# FPGA_HDMI_IN_OUT.net
KiCad netlist of a schematic drawn in Altium Designer
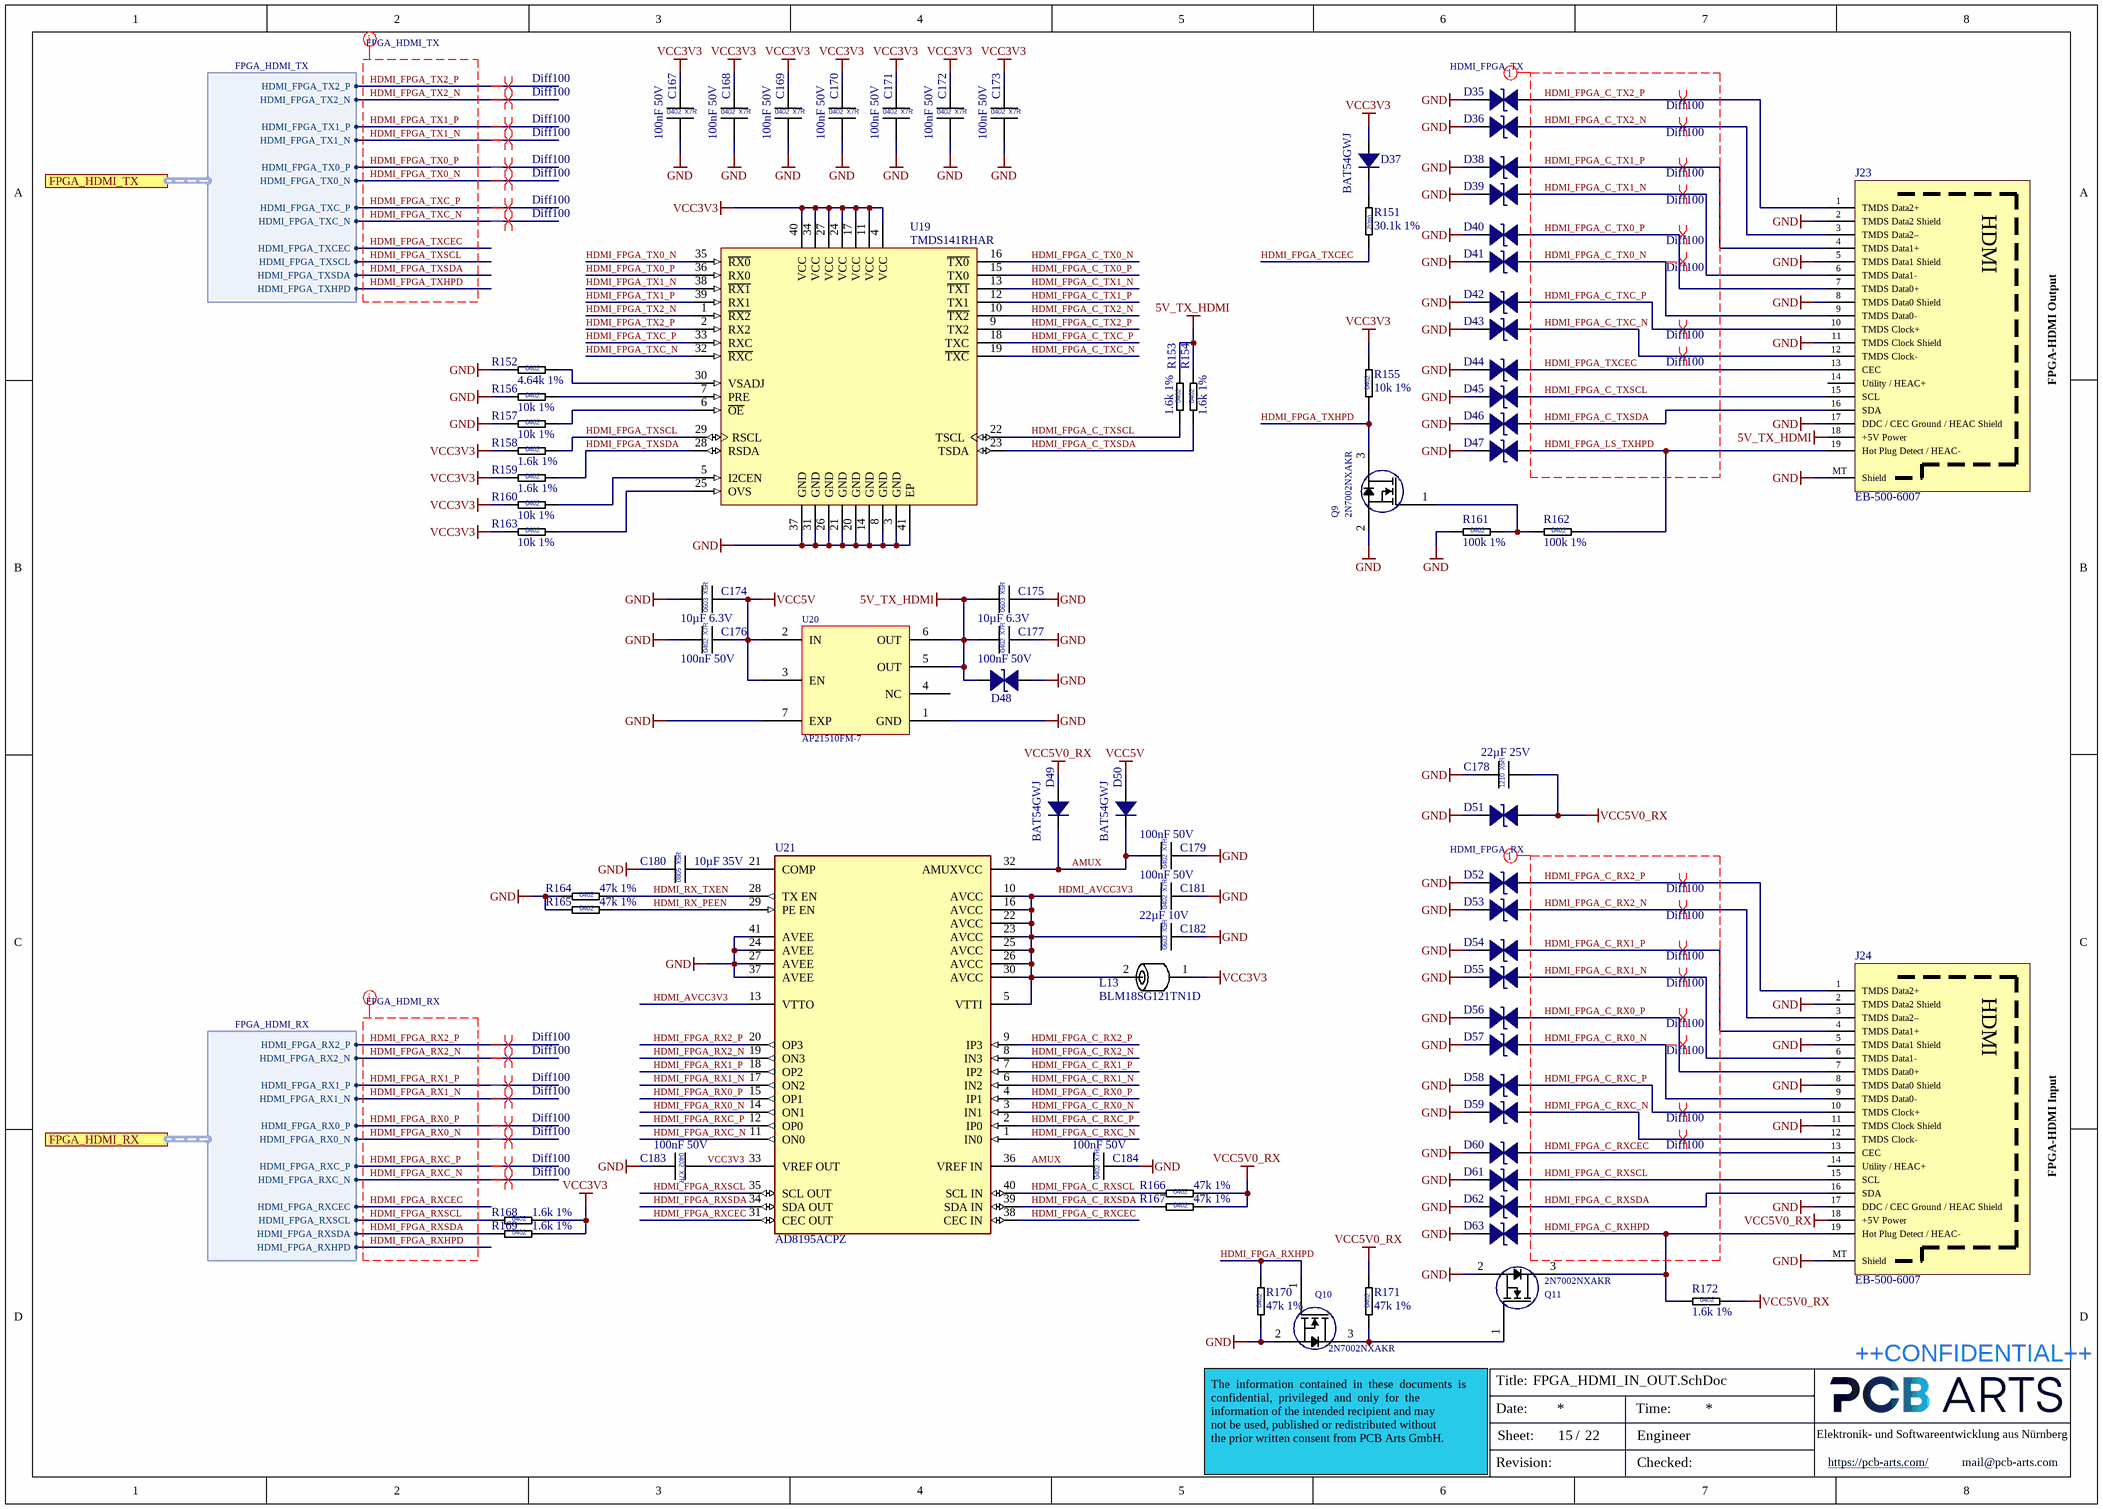
[diagram p0: FPGA_HDMI_IN_OUT.SchDoc]

(export (version "E")
  (design (tool "Eeschema 10.0.6"))
  (components
    (comp (ref "C167")
      (value "100nF 50V")
      (footprint "Cap:CAP_0402_L")
      (description "Multilayer Ceramic Capacitors MLCC - SMD/SMT 0402 50VDC")
      (libsource (lib "") (part "CAP_0402_100nF_50V_1"))
    )
    (comp (ref "C168")
      (value "100nF 50V")
      (footprint "Cap:CAP_0402_L")
      (description "Multilayer Ceramic Capacitors MLCC - SMD/SMT 0402 50VDC")
      (libsource (lib "") (part "CAP_0402_100nF_50V_1"))
    )
    (comp (ref "C169")
      (value "100nF 50V")
      (footprint "Cap:CAP_0402_L")
      (description "Multilayer Ceramic Capacitors MLCC - SMD/SMT 0402 50VDC")
      (libsource (lib "") (part "CAP_0402_100nF_50V_1"))
    )
    (comp (ref "C170")
      (value "100nF 50V")
      (footprint "Cap:CAP_0402_L")
      (description "Multilayer Ceramic Capacitors MLCC - SMD/SMT 0402 50VDC")
      (libsource (lib "") (part "CAP_0402_100nF_50V_1"))
    )
    (comp (ref "C171")
      (value "100nF 50V")
      (footprint "Cap:CAP_0402_L")
      (description "Multilayer Ceramic Capacitors MLCC - SMD/SMT 0402 50VDC")
      (libsource (lib "") (part "CAP_0402_100nF_50V_1"))
    )
    (comp (ref "C172")
      (value "100nF 50V")
      (footprint "Cap:CAP_0402_L")
      (description "Multilayer Ceramic Capacitors MLCC - SMD/SMT 0402 50VDC")
      (libsource (lib "") (part "CAP_0402_100nF_50V_1"))
    )
    (comp (ref "C173")
      (value "100nF 50V")
      (footprint "Cap:CAP_0402_L")
      (description "Multilayer Ceramic Capacitors MLCC - SMD/SMT 0402 50VDC")
      (libsource (lib "") (part "CAP_0402_100nF_50V_1"))
    )
    (comp (ref "C174")
      (value "10µF 6.3V")
      (footprint "Cap:CAP_0603_L")
      (description "Multilayer Ceramic Capacitors MLCC - SMD/SMT 0603 6.3VDC")
      (libsource (lib "Cap") (part "CAP_0603_10µF_6.3V"))
    )
    (comp (ref "C175")
      (value "10µF 6.3V")
      (footprint "Cap:CAP_0603_L")
      (description "Multilayer Ceramic Capacitors MLCC - SMD/SMT 0603 6.3VDC")
      (libsource (lib "Cap") (part "CAP_0603_10µF_6.3V"))
    )
    (comp (ref "C176")
      (value "100nF 50V")
      (footprint "Cap:CAP_0402_L")
      (description "Multilayer Ceramic Capacitors MLCC - SMD/SMT 0402 50VDC")
      (libsource (lib "Cap") (part "CAP_0402_100nF_50V"))
    )
    (comp (ref "C177")
      (value "100nF 50V")
      (footprint "Cap:CAP_0402_L")
      (description "Multilayer Ceramic Capacitors MLCC - SMD/SMT 0402 50VDC")
      (libsource (lib "Cap") (part "CAP_0402_100nF_50V"))
    )
    (comp (ref "C178")
      (value "22µF 25V")
      (footprint "Cap:CAP_1210")
      (description "Multilayer Ceramic Capacitors MLCC - SMD/SMT 1210 25VDC")
      (libsource (lib "Cap") (part "CAP_1210_22µF_25V"))
    )
    (comp (ref "C179")
      (value "100nF 50V")
      (footprint "Cap:CAP_0402_L")
      (description "Multilayer Ceramic Capacitors MLCC - SMD/SMT 0402 50VDC")
      (libsource (lib "Cap") (part "CAP_0402_100nF_50V"))
    )
    (comp (ref "C180")
      (value "10µF 35V")
      (footprint "Cap:CAP_0805")
      (description "Multilayer Ceramic Capacitors MLCC - SMD/SMT 0805 35VDC")
      (libsource (lib "Cap") (part "CAP_0805_10µF_35V"))
    )
    (comp (ref "C181")
      (value "100nF 50V")
      (footprint "Cap:CAP_0402_L")
      (description "Multilayer Ceramic Capacitors MLCC - SMD/SMT 0402 50VDC")
      (libsource (lib "Cap") (part "CAP_0402_100nF_50V"))
    )
    (comp (ref "C182")
      (value "22µF 10V")
      (footprint "Cap:CAP_0603_L")
      (description "Multilayer Ceramic Capacitors MLCC - SMD/SMT 0603 10VDC")
      (libsource (lib "Cap") (part "CAP_0603_22µF_10V"))
    )
    (comp (ref "C183")
      (value "100nF 50V")
      (footprint "Cap:CAP_0402_L")
      (description "Multilayer Ceramic Capacitors MLCC - SMD/SMT 0402 50VDC")
      (libsource (lib "") (part "CAP_0402_100nF_50V_1"))
    )
    (comp (ref "C184")
      (value "100nF 50V")
      (footprint "Cap:CAP_0402_L")
      (description "Multilayer Ceramic Capacitors MLCC - SMD/SMT 0402 50VDC")
      (libsource (lib "Cap") (part "CAP_0402_100nF_50V"))
    )
    (comp (ref "D35")
      (value "CESDP0402UC5VB")
      (footprint "Protec:TVS_0402")
      (description "Low Capacitance ESD Protection Diode 0402")
      (libsource (lib "Protec") (part "CESDP0402UC5VB_TVS Diode 0402"))
    )
    (comp (ref "D36")
      (value "CESDP0402UC5VB")
      (footprint "Protec:TVS_0402")
      (description "Low Capacitance ESD Protection Diode 0402")
      (libsource (lib "Protec") (part "CESDP0402UC5VB_TVS Diode 0402"))
    )
    (comp (ref "D37")
      (value "BAT54GWJ")
      (footprint "Active:SOD123")
      (description "Schottky Diode 30V, 200mA")
      (libsource (lib "Active") (part "BAT54GWJ_Schottky Diode 30V, 200mA"))
    )
    (comp (ref "D38")
      (value "CESDP0402UC5VB")
      (footprint "Protec:TVS_0402")
      (description "Low Capacitance ESD Protection Diode 0402")
      (libsource (lib "Protec") (part "CESDP0402UC5VB_TVS Diode 0402"))
    )
    (comp (ref "D39")
      (value "CESDP0402UC5VB")
      (footprint "Protec:TVS_0402")
      (description "Low Capacitance ESD Protection Diode 0402")
      (libsource (lib "Protec") (part "CESDP0402UC5VB_TVS Diode 0402"))
    )
    (comp (ref "D40")
      (value "CESDP0402UC5VB")
      (footprint "Protec:TVS_0402")
      (description "Low Capacitance ESD Protection Diode 0402")
      (libsource (lib "Protec") (part "CESDP0402UC5VB_TVS Diode 0402"))
    )
    (comp (ref "D41")
      (value "CESDP0402UC5VB")
      (footprint "Protec:TVS_0402")
      (description "Low Capacitance ESD Protection Diode 0402")
      (libsource (lib "Protec") (part "CESDP0402UC5VB_TVS Diode 0402"))
    )
    (comp (ref "D42")
      (value "CESDP0402UC5VB")
      (footprint "Protec:TVS_0402")
      (description "Low Capacitance ESD Protection Diode 0402")
      (libsource (lib "Protec") (part "CESDP0402UC5VB_TVS Diode 0402"))
    )
    (comp (ref "D43")
      (value "CESDP0402UC5VB")
      (footprint "Protec:TVS_0402")
      (description "Low Capacitance ESD Protection Diode 0402")
      (libsource (lib "Protec") (part "CESDP0402UC5VB_TVS Diode 0402"))
    )
    (comp (ref "D44")
      (value "CESDP0402UC5VB")
      (footprint "Protec:TVS_0402")
      (description "Low Capacitance ESD Protection Diode 0402")
      (libsource (lib "Protec") (part "CESDP0402UC5VB_TVS Diode 0402"))
    )
    (comp (ref "D45")
      (value "CESDP0402UC5VB")
      (footprint "Protec:TVS_0402")
      (description "Low Capacitance ESD Protection Diode 0402")
      (libsource (lib "Protec") (part "CESDP0402UC5VB_TVS Diode 0402"))
    )
    (comp (ref "D46")
      (value "CESDP0402UC5VB")
      (footprint "Protec:TVS_0402")
      (description "Low Capacitance ESD Protection Diode 0402")
      (libsource (lib "Protec") (part "CESDP0402UC5VB_TVS Diode 0402"))
    )
    (comp (ref "D47")
      (value "CESDP0402UC5VB")
      (footprint "Protec:TVS_0402")
      (description "Low Capacitance ESD Protection Diode 0402")
      (libsource (lib "Protec") (part "CESDP0402UC5VB_TVS Diode 0402"))
    )
    (comp (ref "D48")
      (value "CESDP0402UC5VB")
      (footprint "Protec:TVS_0402")
      (description "Low Capacitance ESD Protection Diode 0402")
      (libsource (lib "Protec") (part "CESDP0402UC5VB_TVS Diode 0402"))
    )
    (comp (ref "D49")
      (value "BAT54GWJ")
      (footprint "Active:SOD123")
      (description "Schottky Diode 30V, 200mA")
      (libsource (lib "Active") (part "BAT54GWJ_Schottky Diode 30V, 200mA"))
    )
    (comp (ref "D50")
      (value "BAT54GWJ")
      (footprint "Active:SOD123")
      (description "Schottky Diode 30V, 200mA")
      (libsource (lib "Active") (part "BAT54GWJ_Schottky Diode 30V, 200mA"))
    )
    (comp (ref "D51")
      (value "CESDP0402UC5VB")
      (footprint "Protec:TVS_0402")
      (description "Low Capacitance ESD Protection Diode 0402")
      (libsource (lib "Protec") (part "CESDP0402UC5VB_TVS Diode 0402"))
    )
    (comp (ref "D52")
      (value "CESDP0402UC5VB")
      (footprint "Protec:TVS_0402")
      (description "Low Capacitance ESD Protection Diode 0402")
      (libsource (lib "Protec") (part "CESDP0402UC5VB_TVS Diode 0402"))
    )
    (comp (ref "D53")
      (value "CESDP0402UC5VB")
      (footprint "Protec:TVS_0402")
      (description "Low Capacitance ESD Protection Diode 0402")
      (libsource (lib "Protec") (part "CESDP0402UC5VB_TVS Diode 0402"))
    )
    (comp (ref "D54")
      (value "CESDP0402UC5VB")
      (footprint "Protec:TVS_0402")
      (description "Low Capacitance ESD Protection Diode 0402")
      (libsource (lib "Protec") (part "CESDP0402UC5VB_TVS Diode 0402"))
    )
    (comp (ref "D55")
      (value "CESDP0402UC5VB")
      (footprint "Protec:TVS_0402")
      (description "Low Capacitance ESD Protection Diode 0402")
      (libsource (lib "Protec") (part "CESDP0402UC5VB_TVS Diode 0402"))
    )
    (comp (ref "D56")
      (value "CESDP0402UC5VB")
      (footprint "Protec:TVS_0402")
      (description "Low Capacitance ESD Protection Diode 0402")
      (libsource (lib "Protec") (part "CESDP0402UC5VB_TVS Diode 0402"))
    )
    (comp (ref "D57")
      (value "CESDP0402UC5VB")
      (footprint "Protec:TVS_0402")
      (description "Low Capacitance ESD Protection Diode 0402")
      (libsource (lib "Protec") (part "CESDP0402UC5VB_TVS Diode 0402"))
    )
    (comp (ref "D58")
      (value "CESDP0402UC5VB")
      (footprint "Protec:TVS_0402")
      (description "Low Capacitance ESD Protection Diode 0402")
      (libsource (lib "Protec") (part "CESDP0402UC5VB_TVS Diode 0402"))
    )
    (comp (ref "D59")
      (value "CESDP0402UC5VB")
      (footprint "Protec:TVS_0402")
      (description "Low Capacitance ESD Protection Diode 0402")
      (libsource (lib "Protec") (part "CESDP0402UC5VB_TVS Diode 0402"))
    )
    (comp (ref "D60")
      (value "CESDP0402UC5VB")
      (footprint "Protec:TVS_0402")
      (description "Low Capacitance ESD Protection Diode 0402")
      (libsource (lib "Protec") (part "CESDP0402UC5VB_TVS Diode 0402"))
    )
    (comp (ref "D61")
      (value "CESDP0402UC5VB")
      (footprint "Protec:TVS_0402")
      (description "Low Capacitance ESD Protection Diode 0402")
      (libsource (lib "Protec") (part "CESDP0402UC5VB_TVS Diode 0402"))
    )
    (comp (ref "D62")
      (value "CESDP0402UC5VB")
      (footprint "Protec:TVS_0402")
      (description "Low Capacitance ESD Protection Diode 0402")
      (libsource (lib "Protec") (part "CESDP0402UC5VB_TVS Diode 0402"))
    )
    (comp (ref "D63")
      (value "CESDP0402UC5VB")
      (footprint "Protec:TVS_0402")
      (description "Low Capacitance ESD Protection Diode 0402")
      (libsource (lib "Protec") (part "CESDP0402UC5VB_TVS Diode 0402"))
    )
    (comp (ref "J23")
      (value "EB-500-6007")
      (footprint "Conn:Elecbee EB-500-6007")
      (description "HDMI Connector Female Vertical 19 Pin")
      (libsource (lib "Conn") (part "EB-500-6007_HDMI Connector 19Pin Vertical THT"))
    )
    (comp (ref "J24")
      (value "EB-500-6007")
      (footprint "Conn:Elecbee EB-500-6007")
      (description "HDMI Connector Female Vertical 19 Pin")
      (libsource (lib "Conn") (part "EB-500-6007_HDMI Connector 19Pin Vertical THT"))
    )
    (comp (ref "L13")
      (value "BLM18SG121TN1D")
      (footprint "Indc:L_0603")
      (description "Ferritperlen BLM18_xN 0603 100MHz 120Ohm 3000mA 25mOhm RSER")
      (libsource (lib "Indc") (part "BLM18SG121TN1D_Ferrite Beads 0603 120Ohms 3000mA"))
    )
    (comp (ref "Q9")
      (value "2N7002NXAKR")
      (footprint "trans:SOT95P251X112-3N")
      (description "MOSFET 60V SGL N-CH TRENCHMOS")
      (libsource (lib "Trans") (part "2N7002NXAKR_MOSFET 60V SGL N-CH TRENCHMOS"))
    )
    (comp (ref "Q10")
      (value "2N7002NXAKR")
      (footprint "trans:SOT95P251X112-3N")
      (description "MOSFET 60V SGL N-CH TRENCHMOS")
      (libsource (lib "Trans") (part "2N7002NXAKR_MOSFET 60V SGL N-CH TRENCHMOS"))
    )
    (comp (ref "Q11")
      (value "2N7002NXAKR")
      (footprint "trans:SOT95P251X112-3N")
      (description "MOSFET 60V SGL N-CH TRENCHMOS")
      (libsource (lib "") (part "2N7002NXAKR_MOSFET 60V SGL N-CH TRENCHMOS_1"))
    )
    (comp (ref "R151")
      (value "30.1k 1%")
      (footprint "Res:RES_0402_L")
      (description "Thick Film Resistors - SMD 30.1kOhm 1%")
      (libsource (lib "Res") (part "RES_0402_30.1k_1%"))
    )
    (comp (ref "R152")
      (value "4.64k 1%")
      (footprint "Res:RES_0402_L")
      (description "Thick Film Resistors - SMD 4.64kOhm 1%")
      (libsource (lib "Res") (part "RES_0402_4.64k_1%"))
    )
    (comp (ref "R153")
      (value "1.6k 1%")
      (footprint "Res:RES_0402_L")
      (description "Thick Film Resistors - SMD 1.6kOhm 1%")
      (libsource (lib "Res") (part "RES_0402_1.6k_1%"))
    )
    (comp (ref "R154")
      (value "1.6k 1%")
      (footprint "Res:RES_0402_L")
      (description "Thick Film Resistors - SMD 1.6kOhm 1%")
      (libsource (lib "Res") (part "RES_0402_1.6k_1%"))
    )
    (comp (ref "R155")
      (value "10k 1%")
      (footprint "Res:RES_0402_L")
      (description "Thick Film Resistors - SMD 10kOhm 1%")
      (libsource (lib "Res") (part "RES_0402_10k_1%"))
    )
    (comp (ref "R156")
      (value "10k 1%")
      (footprint "Res:RES_0402_L")
      (description "Thick Film Resistors - SMD 10kOhm 1%")
      (libsource (lib "Res") (part "RES_0402_10k_1%"))
    )
    (comp (ref "R157")
      (value "10k 1%")
      (footprint "Res:RES_0402_L")
      (description "Thick Film Resistors - SMD 10kOhm 1%")
      (libsource (lib "Res") (part "RES_0402_10k_1%"))
    )
    (comp (ref "R158")
      (value "1.6k 1%")
      (footprint "Res:RES_0402_L")
      (description "Thick Film Resistors - SMD 1.6kOhm 1%")
      (libsource (lib "Res") (part "RES_0402_1.6k_1%"))
    )
    (comp (ref "R159")
      (value "1.6k 1%")
      (footprint "Res:RES_0402_L")
      (description "Thick Film Resistors - SMD 1.6kOhm 1%")
      (libsource (lib "Res") (part "RES_0402_1.6k_1%"))
    )
    (comp (ref "R160")
      (value "10k 1%")
      (footprint "Res:RES_0402_L")
      (description "Thick Film Resistors - SMD 10kOhm 1%")
      (libsource (lib "Res") (part "RES_0402_10k_1%"))
    )
    (comp (ref "R161")
      (value "100k 1%")
      (footprint "Res:RES_0402_L")
      (description "Thick Film Resistors - SMD 100kOhm 1%")
      (libsource (lib "Res") (part "RES_0402_100k_1%"))
    )
    (comp (ref "R162")
      (value "100k 1%")
      (footprint "Res:RES_0402_L")
      (description "Thick Film Resistors - SMD 100kOhm 1%")
      (libsource (lib "Res") (part "RES_0402_100k_1%"))
    )
    (comp (ref "R163")
      (value "10k 1%")
      (footprint "Res:RES_0402_L")
      (description "Thick Film Resistors - SMD 10kOhm 1%")
      (libsource (lib "Res") (part "RES_0402_10k_1%"))
    )
    (comp (ref "R164")
      (value "47k 1%")
      (footprint "Res:RES_0402_L")
      (description "Thick Film Resistors - SMD 47kOhm 1%")
      (libsource (lib "Res") (part "RES_0402_47k_1%"))
    )
    (comp (ref "R165")
      (value "47k 1%")
      (footprint "Res:RES_0402_L")
      (description "Thick Film Resistors - SMD 47kOhm 1%")
      (libsource (lib "Res") (part "RES_0402_47k_1%"))
    )
    (comp (ref "R166")
      (value "47k 1%")
      (footprint "Res:RES_0402_L")
      (description "Thick Film Resistors - SMD 47kOhm 1%")
      (libsource (lib "Res") (part "RES_0402_47k_1%"))
    )
    (comp (ref "R167")
      (value "47k 1%")
      (footprint "Res:RES_0402_L")
      (description "Thick Film Resistors - SMD 47kOhm 1%")
      (libsource (lib "Res") (part "RES_0402_47k_1%"))
    )
    (comp (ref "R168")
      (value "1.6k 1%")
      (footprint "Res:RES_0402_L")
      (description "Thick Film Resistors - SMD 1.6kOhm 1%")
      (libsource (lib "Res") (part "RES_0402_1.6k_1%"))
    )
    (comp (ref "R169")
      (value "1.6k 1%")
      (footprint "Res:RES_0402_L")
      (description "Thick Film Resistors - SMD 1.6kOhm 1%")
      (libsource (lib "Res") (part "RES_0402_1.6k_1%"))
    )
    (comp (ref "R170")
      (value "47k 1%")
      (footprint "Res:RES_0402_L")
      (description "Thick Film Resistors - SMD 47kOhm 1%")
      (libsource (lib "Res") (part "RES_0402_47k_1%"))
    )
    (comp (ref "R171")
      (value "47k 1%")
      (footprint "Res:RES_0402_L")
      (description "Thick Film Resistors - SMD 47kOhm 1%")
      (libsource (lib "Res") (part "RES_0402_47k_1%"))
    )
    (comp (ref "R172")
      (value "1.6k 1%")
      (footprint "Res:RES_0402_L")
      (description "Thick Film Resistors - SMD 1.6kOhm 1%")
      (libsource (lib "Res") (part "RES_0402_1.6k_1%"))
    )
    (comp (ref "U19")
      (value "TMDS141RHAR")
      (footprint "Digital:QFN50P600X600X100-41N")
      (description "HDMI Hider, 130 mA, 6 kV, 0 to +70 degC, 40-pin QFN")
      (libsource (lib "Digital") (part "TMDS141RHAR_HDMI Hider, 130 mA, 6 kV, 0 to +70 degC, 40-pin QFN"))
    )
    (comp (ref "U20")
      (value "AP21510FM-7")
      (footprint "Power:QFN50P201X181X60_HS-7N")
      (description "Power Switch ICs - Power Distribution 0.5A SGL Ch USB 2.0 Curr Limited Switch")
      (libsource (lib "Power") (part "AP21510FM-7_Power Switch ICs - Power Distribution Load Switch"))
    )
    (comp (ref "U21")
      (value "AD8195ACPZ")
      (footprint "Digital:QFN50P600X600X100-41N")
      (description "IC VIDEO HDMI/DVI BUFFER 40LFCSP")
      (libsource (lib "Digital") (part "AD8195ACPZ_IC VIDEO HDMI/DVI BUFFER 40LFCSP"))
    )
  )
  (nets
    (net (code "3") (name "/AMUX") (class "Default")
      (node (ref "C179") (pin "1") (pinfunction "1_1") (pintype "passive"))
      (node (ref "C184") (pin "1") (pinfunction "1_1") (pintype "passive"))
      (node (ref "D49") (pin "1") (pinfunction "1_1") (pintype "passive"))
      (node (ref "D50") (pin "1") (pinfunction "1_1") (pintype "passive"))
      (node (ref "U21") (pin "32") (pinfunction "AMUXVCC_32") (pintype "power_in"))
      (node (ref "U21") (pin "36") (pinfunction "VREF_IN_36") (pintype "passive"))
    )
    (net (code "4") (name "/HDMI_AVCC3V3") (class "Default")
      (node (ref "C181") (pin "1") (pinfunction "1_1") (pintype "passive"))
      (node (ref "C182") (pin "1") (pinfunction "1_1") (pintype "passive"))
      (node (ref "L13") (pin "2") (pinfunction "2_2") (pintype "passive"))
      (node (ref "U21") (pin "10") (pinfunction "AVCC_10") (pintype "power_in"))
      (node (ref "U21") (pin "13") (pinfunction "VTTO_13") (pintype "power_in"))
      (node (ref "U21") (pin "16") (pinfunction "AVCC_16") (pintype "power_in"))
      (node (ref "U21") (pin "22") (pinfunction "AVCC_22") (pintype "power_in"))
      (node (ref "U21") (pin "23") (pinfunction "AVCC_23") (pintype "power_in"))
      (node (ref "U21") (pin "25") (pinfunction "AVCC_25") (pintype "power_in"))
      (node (ref "U21") (pin "26") (pinfunction "AVCC_26") (pintype "power_in"))
      (node (ref "U21") (pin "30") (pinfunction "AVCC_30") (pintype "power_in"))
      (node (ref "U21") (pin "5") (pinfunction "VTTI_5") (pintype "power_in"))
    )
    (net (code "5") (name "/HDMI_FPGA_C_RX0_N") (class "Default")
      (node (ref "D57") (pin "2") (pinfunction "2_2") (pintype "passive"))
      (node (ref "J24") (pin "9") (pinfunction "TMDS_Data0-_9") (pintype "passive"))
      (node (ref "U21") (pin "3") (pinfunction "IN1_3") (pintype "input"))
    )
    (net (code "6") (name "/HDMI_FPGA_C_RX0_P") (class "Default")
      (node (ref "D56") (pin "2") (pinfunction "2_2") (pintype "passive"))
      (node (ref "J24") (pin "7") (pinfunction "TMDS_Data0+_7") (pintype "passive"))
      (node (ref "U21") (pin "4") (pinfunction "IP1_4") (pintype "input"))
    )
    (net (code "7") (name "/HDMI_FPGA_C_RX1_N") (class "Default")
      (node (ref "D55") (pin "2") (pinfunction "2_2") (pintype "passive"))
      (node (ref "J24") (pin "6") (pinfunction "TMDS_Data1-_6") (pintype "passive"))
      (node (ref "U21") (pin "6") (pinfunction "IN2_6") (pintype "input"))
    )
    (net (code "8") (name "/HDMI_FPGA_C_RX1_P") (class "Default")
      (node (ref "D54") (pin "2") (pinfunction "2_2") (pintype "passive"))
      (node (ref "J24") (pin "4") (pinfunction "TMDS_Data1+_4") (pintype "passive"))
      (node (ref "U21") (pin "7") (pinfunction "IP2_7") (pintype "input"))
    )
    (net (code "9") (name "/HDMI_FPGA_C_RX2_N") (class "Default")
      (node (ref "D53") (pin "2") (pinfunction "2_2") (pintype "passive"))
      (node (ref "J24") (pin "3") (pinfunction "TMDS_Data2–_3") (pintype "passive"))
      (node (ref "U21") (pin "8") (pinfunction "IN3_8") (pintype "input"))
    )
    (net (code "10") (name "/HDMI_FPGA_C_RX2_P") (class "Default")
      (node (ref "D52") (pin "2") (pinfunction "2_2") (pintype "passive"))
      (node (ref "J24") (pin "1") (pinfunction "TMDS_Data2+_1") (pintype "passive"))
      (node (ref "U21") (pin "9") (pinfunction "IP3_9") (pintype "input"))
    )
    (net (code "11") (name "/HDMI_FPGA_C_RXCEC") (class "Default")
      (node (ref "D60") (pin "2") (pinfunction "2_2") (pintype "passive"))
      (node (ref "J24") (pin "13") (pinfunction "CEC_13") (pintype "passive"))
      (node (ref "U21") (pin "38") (pinfunction "CEC_IN_38") (pintype "bidirectional"))
    )
    (net (code "12") (name "/HDMI_FPGA_C_RXC_N") (class "Default")
      (node (ref "D59") (pin "2") (pinfunction "2_2") (pintype "passive"))
      (node (ref "J24") (pin "12") (pinfunction "TMDS_Clock-_12") (pintype "passive"))
      (node (ref "U21") (pin "1") (pinfunction "IN0_1") (pintype "input"))
    )
    (net (code "13") (name "/HDMI_FPGA_C_RXC_P") (class "Default")
      (node (ref "D58") (pin "2") (pinfunction "2_2") (pintype "passive"))
      (node (ref "J24") (pin "10") (pinfunction "TMDS_Clock+_10") (pintype "passive"))
      (node (ref "U21") (pin "2") (pinfunction "IP0_2") (pintype "input"))
    )
    (net (code "14") (name "/HDMI_FPGA_C_RXHPD") (class "Default")
      (node (ref "D63") (pin "2") (pinfunction "2_2") (pintype "passive"))
      (node (ref "J24") (pin "19") (pinfunction "Hot_Plug_Detect_/_HEAC-_19") (pintype "passive"))
      (node (ref "Q11") (pin "3") (pinfunction "D_3") (pintype "passive"))
      (node (ref "R172") (pin "1") (pinfunction "1_1") (pintype "passive"))
    )
    (net (code "15") (name "/HDMI_FPGA_C_RXSCL") (class "Default")
      (node (ref "D61") (pin "2") (pinfunction "2_2") (pintype "passive"))
      (node (ref "J24") (pin "15") (pinfunction "SCL_15") (pintype "passive"))
      (node (ref "R166") (pin "1") (pinfunction "1_1") (pintype "passive"))
      (node (ref "U21") (pin "40") (pinfunction "SCL_IN_40") (pintype "bidirectional"))
    )
    (net (code "16") (name "/HDMI_FPGA_C_RXSDA") (class "Default")
      (node (ref "D62") (pin "2") (pinfunction "2_2") (pintype "passive"))
      (node (ref "J24") (pin "16") (pinfunction "SDA_16") (pintype "passive"))
      (node (ref "R167") (pin "1") (pinfunction "1_1") (pintype "passive"))
      (node (ref "U21") (pin "39") (pinfunction "SDA_IN_39") (pintype "bidirectional"))
    )
    (net (code "17") (name "/HDMI_FPGA_C_TX0_N") (class "Default")
      (node (ref "D41") (pin "2") (pinfunction "2_2") (pintype "passive"))
      (node (ref "J23") (pin "9") (pinfunction "TMDS_Data0-_9") (pintype "passive"))
      (node (ref "U19") (pin "16") (pinfunction "~{TX0}_16") (pintype "tri_state"))
    )
    (net (code "18") (name "/HDMI_FPGA_C_TX0_P") (class "Default")
      (node (ref "D40") (pin "2") (pinfunction "2_2") (pintype "passive"))
      (node (ref "J23") (pin "7") (pinfunction "TMDS_Data0+_7") (pintype "passive"))
      (node (ref "U19") (pin "15") (pinfunction "TX0_15") (pintype "tri_state"))
    )
    (net (code "19") (name "/HDMI_FPGA_C_TX1_N") (class "Default")
      (node (ref "D39") (pin "2") (pinfunction "2_2") (pintype "passive"))
      (node (ref "J23") (pin "6") (pinfunction "TMDS_Data1-_6") (pintype "passive"))
      (node (ref "U19") (pin "13") (pinfunction "~{TX1}_13") (pintype "tri_state"))
    )
    (net (code "20") (name "/HDMI_FPGA_C_TX1_P") (class "Default")
      (node (ref "D38") (pin "2") (pinfunction "2_2") (pintype "passive"))
      (node (ref "J23") (pin "4") (pinfunction "TMDS_Data1+_4") (pintype "passive"))
      (node (ref "U19") (pin "12") (pinfunction "TX1_12") (pintype "tri_state"))
    )
    (net (code "21") (name "/HDMI_FPGA_C_TX2_N") (class "Default")
      (node (ref "D36") (pin "2") (pinfunction "2_2") (pintype "passive"))
      (node (ref "J23") (pin "3") (pinfunction "TMDS_Data2–_3") (pintype "passive"))
      (node (ref "U19") (pin "10") (pinfunction "~{TX2}_10") (pintype "tri_state"))
    )
    (net (code "22") (name "/HDMI_FPGA_C_TX2_P") (class "Default")
      (node (ref "D35") (pin "2") (pinfunction "2_2") (pintype "passive"))
      (node (ref "J23") (pin "1") (pinfunction "TMDS_Data2+_1") (pintype "passive"))
      (node (ref "U19") (pin "9") (pinfunction "TX2_9") (pintype "tri_state"))
    )
    (net (code "23") (name "/HDMI_FPGA_C_TXC_N") (class "Default")
      (node (ref "D43") (pin "2") (pinfunction "2_2") (pintype "passive"))
      (node (ref "J23") (pin "12") (pinfunction "TMDS_Clock-_12") (pintype "passive"))
      (node (ref "U19") (pin "19") (pinfunction "~{TXC}_19") (pintype "tri_state"))
    )
    (net (code "24") (name "/HDMI_FPGA_C_TXC_P") (class "Default")
      (node (ref "D42") (pin "2") (pinfunction "2_2") (pintype "passive"))
      (node (ref "J23") (pin "10") (pinfunction "TMDS_Clock+_10") (pintype "passive"))
      (node (ref "U19") (pin "18") (pinfunction "TXC_18") (pintype "tri_state"))
    )
    (net (code "25") (name "/HDMI_FPGA_C_TXSCL") (class "Default")
      (node (ref "D45") (pin "2") (pinfunction "2_2") (pintype "passive"))
      (node (ref "J23") (pin "15") (pinfunction "SCL_15") (pintype "passive"))
      (node (ref "R153") (pin "1") (pinfunction "1_1") (pintype "passive"))
      (node (ref "U19") (pin "22") (pinfunction "TSCL_22") (pintype "bidirectional"))
    )
    (net (code "26") (name "/HDMI_FPGA_C_TXSDA") (class "Default")
      (node (ref "D46") (pin "2") (pinfunction "2_2") (pintype "passive"))
      (node (ref "J23") (pin "16") (pinfunction "SDA_16") (pintype "passive"))
      (node (ref "R154") (pin "1") (pinfunction "1_1") (pintype "passive"))
      (node (ref "U19") (pin "23") (pinfunction "TSDA_23") (pintype "bidirectional"))
    )
    (net (code "27") (name "/HDMI_FPGA_LS_TXHPD") (class "Default")
      (node (ref "D47") (pin "2") (pinfunction "2_2") (pintype "passive"))
      (node (ref "J23") (pin "19") (pinfunction "Hot_Plug_Detect_/_HEAC-_19") (pintype "passive"))
      (node (ref "R162") (pin "2") (pinfunction "2_2") (pintype "passive"))
    )
    (net (code "28") (name "/HDMI_FPGA_RX0_N") (class "Default")
      (node (ref "U21") (pin "14") (pinfunction "ON1_14") (pintype "output"))
    )
    (net (code "29") (name "/HDMI_FPGA_RX0_P") (class "Default")
      (node (ref "U21") (pin "15") (pinfunction "OP1_15") (pintype "output"))
    )
    (net (code "30") (name "/HDMI_FPGA_RX1_N") (class "Default")
      (node (ref "U21") (pin "17") (pinfunction "ON2_17") (pintype "output"))
    )
    (net (code "31") (name "/HDMI_FPGA_RX1_P") (class "Default")
      (node (ref "U21") (pin "18") (pinfunction "OP2_18") (pintype "output"))
    )
    (net (code "32") (name "/HDMI_FPGA_RX2_N") (class "Default")
      (node (ref "U21") (pin "19") (pinfunction "ON3_19") (pintype "output"))
    )
    (net (code "33") (name "/HDMI_FPGA_RX2_P") (class "Default")
      (node (ref "U21") (pin "20") (pinfunction "OP3_20") (pintype "output"))
    )
    (net (code "34") (name "/HDMI_FPGA_RXCEC") (class "Default")
      (node (ref "U21") (pin "31") (pinfunction "CEC_OUT_31") (pintype "bidirectional"))
    )
    (net (code "35") (name "/HDMI_FPGA_RXC_N") (class "Default")
      (node (ref "U21") (pin "11") (pinfunction "ON0_11") (pintype "output"))
    )
    (net (code "36") (name "/HDMI_FPGA_RXC_P") (class "Default")
      (node (ref "U21") (pin "12") (pinfunction "OP0_12") (pintype "output"))
    )
    (net (code "37") (name "/HDMI_FPGA_RXHPD") (class "Default")
      (node (ref "Q10") (pin "1") (pinfunction "G_1") (pintype "passive"))
      (node (ref "R170") (pin "2") (pinfunction "2_2") (pintype "passive"))
    )
    (net (code "38") (name "/HDMI_FPGA_RXSCL") (class "Default")
      (node (ref "R168") (pin "1") (pinfunction "1_1") (pintype "passive"))
      (node (ref "U21") (pin "35") (pinfunction "SCL_OUT_35") (pintype "bidirectional"))
    )
    (net (code "39") (name "/HDMI_FPGA_RXSDA") (class "Default")
      (node (ref "R169") (pin "1") (pinfunction "1_1") (pintype "passive"))
      (node (ref "U21") (pin "34") (pinfunction "SDA_OUT_34") (pintype "bidirectional"))
    )
    (net (code "40") (name "/HDMI_FPGA_TX0_N") (class "Default")
      (node (ref "U19") (pin "35") (pinfunction "~{RX0}_35") (pintype "input"))
    )
    (net (code "41") (name "/HDMI_FPGA_TX0_P") (class "Default")
      (node (ref "U19") (pin "36") (pinfunction "RX0_36") (pintype "input"))
    )
    (net (code "42") (name "/HDMI_FPGA_TX1_N") (class "Default")
      (node (ref "U19") (pin "38") (pinfunction "~{RX1}_38") (pintype "input"))
    )
    (net (code "43") (name "/HDMI_FPGA_TX1_P") (class "Default")
      (node (ref "U19") (pin "39") (pinfunction "RX1_39") (pintype "input"))
    )
    (net (code "44") (name "/HDMI_FPGA_TX2_N") (class "Default")
      (node (ref "U19") (pin "1") (pinfunction "~{RX2}_1") (pintype "input"))
    )
    (net (code "45") (name "/HDMI_FPGA_TX2_P") (class "Default")
      (node (ref "U19") (pin "2") (pinfunction "RX2_2") (pintype "input"))
    )
    (net (code "46") (name "/HDMI_FPGA_TXCEC") (class "Default")
      (node (ref "D44") (pin "2") (pinfunction "2_2") (pintype "passive"))
      (node (ref "J23") (pin "13") (pinfunction "CEC_13") (pintype "passive"))
      (node (ref "R151") (pin "2") (pinfunction "2_2") (pintype "passive"))
    )
    (net (code "47") (name "/HDMI_FPGA_TXC_N") (class "Default")
      (node (ref "U19") (pin "32") (pinfunction "~{RXC}_32") (pintype "input"))
    )
    (net (code "48") (name "/HDMI_FPGA_TXC_P") (class "Default")
      (node (ref "U19") (pin "33") (pinfunction "RXC_33") (pintype "input"))
    )
    (net (code "49") (name "/HDMI_FPGA_TXHPD") (class "Default")
      (node (ref "Q9") (pin "3") (pinfunction "D_3") (pintype "passive"))
      (node (ref "R155") (pin "1") (pinfunction "1_1") (pintype "passive"))
    )
    (net (code "50") (name "/HDMI_FPGA_TXSCL") (class "Default")
      (node (ref "R158") (pin "2") (pinfunction "2_2") (pintype "passive"))
      (node (ref "U19") (pin "29") (pinfunction "RSCL_29") (pintype "bidirectional"))
    )
    (net (code "51") (name "/HDMI_FPGA_TXSDA") (class "Default")
      (node (ref "R159") (pin "2") (pinfunction "2_2") (pintype "passive"))
      (node (ref "U19") (pin "28") (pinfunction "RSDA_28") (pintype "bidirectional"))
    )
    (net (code "52") (name "/HDMI_RX_PEEN") (class "Default")
      (node (ref "R165") (pin "2") (pinfunction "2_2") (pintype "passive"))
      (node (ref "U21") (pin "29") (pinfunction "PE_EN_29") (pintype "input"))
    )
    (net (code "53") (name "/HDMI_RX_TXEN") (class "Default")
      (node (ref "R164") (pin "2") (pinfunction "2_2") (pintype "passive"))
      (node (ref "U21") (pin "28") (pinfunction "TX_EN_28") (pintype "output"))
    )
    (net (code "56") (name "5V_TX_HDMI") (class "Default")
      (node (ref "C175") (pin "1") (pinfunction "1_1") (pintype "passive"))
      (node (ref "C177") (pin "1") (pinfunction "1_1") (pintype "passive"))
      (node (ref "D48") (pin "1") (pinfunction "1_1") (pintype "passive"))
      (node (ref "J23") (pin "18") (pinfunction "+5V_Power_18") (pintype "passive"))
      (node (ref "R153") (pin "2") (pinfunction "2_2") (pintype "passive"))
      (node (ref "R154") (pin "2") (pinfunction "2_2") (pintype "passive"))
      (node (ref "U20") (pin "5") (pinfunction "OUT_5") (pintype "power_in"))
      (node (ref "U20") (pin "6") (pinfunction "OUT_6") (pintype "power_in"))
    )
    (net (code "57") (name "GND") (class "Default")
      (node (ref "C167") (pin "2") (pinfunction "2_2") (pintype "passive"))
      (node (ref "C168") (pin "2") (pinfunction "2_2") (pintype "passive"))
      (node (ref "C169") (pin "2") (pinfunction "2_2") (pintype "passive"))
      (node (ref "C170") (pin "2") (pinfunction "2_2") (pintype "passive"))
      (node (ref "C171") (pin "2") (pinfunction "2_2") (pintype "passive"))
      (node (ref "C172") (pin "2") (pinfunction "2_2") (pintype "passive"))
      (node (ref "C173") (pin "2") (pinfunction "2_2") (pintype "passive"))
      (node (ref "C174") (pin "1") (pinfunction "1_1") (pintype "passive"))
      (node (ref "C175") (pin "2") (pinfunction "2_2") (pintype "passive"))
      (node (ref "C176") (pin "1") (pinfunction "1_1") (pintype "passive"))
      (node (ref "C177") (pin "2") (pinfunction "2_2") (pintype "passive"))
      (node (ref "C178") (pin "1") (pinfunction "1_1") (pintype "passive"))
      (node (ref "C179") (pin "2") (pinfunction "2_2") (pintype "passive"))
      (node (ref "C180") (pin "1") (pinfunction "1_1") (pintype "passive"))
      (node (ref "C181") (pin "2") (pinfunction "2_2") (pintype "passive"))
      (node (ref "C182") (pin "2") (pinfunction "2_2") (pintype "passive"))
      (node (ref "C183") (pin "2") (pinfunction "2_2") (pintype "passive"))
      (node (ref "C184") (pin "2") (pinfunction "2_2") (pintype "passive"))
      (node (ref "D35") (pin "1") (pinfunction "1_1") (pintype "passive"))
      (node (ref "D36") (pin "1") (pinfunction "1_1") (pintype "passive"))
      (node (ref "D38") (pin "1") (pinfunction "1_1") (pintype "passive"))
      (node (ref "D39") (pin "1") (pinfunction "1_1") (pintype "passive"))
      (node (ref "D40") (pin "1") (pinfunction "1_1") (pintype "passive"))
      (node (ref "D41") (pin "1") (pinfunction "1_1") (pintype "passive"))
      (node (ref "D42") (pin "1") (pinfunction "1_1") (pintype "passive"))
      (node (ref "D43") (pin "1") (pinfunction "1_1") (pintype "passive"))
      (node (ref "D44") (pin "1") (pinfunction "1_1") (pintype "passive"))
      (node (ref "D45") (pin "1") (pinfunction "1_1") (pintype "passive"))
      (node (ref "D46") (pin "1") (pinfunction "1_1") (pintype "passive"))
      (node (ref "D47") (pin "1") (pinfunction "1_1") (pintype "passive"))
      (node (ref "D48") (pin "2") (pinfunction "2_2") (pintype "passive"))
      (node (ref "D51") (pin "1") (pinfunction "1_1") (pintype "passive"))
      (node (ref "D52") (pin "1") (pinfunction "1_1") (pintype "passive"))
      (node (ref "D53") (pin "1") (pinfunction "1_1") (pintype "passive"))
      (node (ref "D54") (pin "1") (pinfunction "1_1") (pintype "passive"))
      (node (ref "D55") (pin "1") (pinfunction "1_1") (pintype "passive"))
      (node (ref "D56") (pin "1") (pinfunction "1_1") (pintype "passive"))
      (node (ref "D57") (pin "1") (pinfunction "1_1") (pintype "passive"))
      (node (ref "D58") (pin "1") (pinfunction "1_1") (pintype "passive"))
      (node (ref "D59") (pin "1") (pinfunction "1_1") (pintype "passive"))
      (node (ref "D60") (pin "1") (pinfunction "1_1") (pintype "passive"))
      (node (ref "D61") (pin "1") (pinfunction "1_1") (pintype "passive"))
      (node (ref "D62") (pin "1") (pinfunction "1_1") (pintype "passive"))
      (node (ref "D63") (pin "1") (pinfunction "1_1") (pintype "passive"))
      (node (ref "J23") (pin "11") (pinfunction "TMDS_Clock_Shield_11") (pintype "passive"))
      (node (ref "J23") (pin "17") (pinfunction "DDC_/_CEC_Ground_/_HEAC_Shield_17") (pintype "passive"))
      (node (ref "J23") (pin "2") (pinfunction "TMDS_Data2_Shield_2") (pintype "passive"))
      (node (ref "J23") (pin "5") (pinfunction "TMDS_Data1_Shield_5") (pintype "passive"))
      (node (ref "J23") (pin "8") (pinfunction "TMDS_Data0_Shield_8") (pintype "passive"))
      (node (ref "J23") (pin "MT") (pinfunction "Shield_MT") (pintype "passive"))
      (node (ref "J24") (pin "11") (pinfunction "TMDS_Clock_Shield_11") (pintype "passive"))
      (node (ref "J24") (pin "17") (pinfunction "DDC_/_CEC_Ground_/_HEAC_Shield_17") (pintype "passive"))
      (node (ref "J24") (pin "2") (pinfunction "TMDS_Data2_Shield_2") (pintype "passive"))
      (node (ref "J24") (pin "5") (pinfunction "TMDS_Data1_Shield_5") (pintype "passive"))
      (node (ref "J24") (pin "8") (pinfunction "TMDS_Data0_Shield_8") (pintype "passive"))
      (node (ref "J24") (pin "MT") (pinfunction "Shield_MT") (pintype "passive"))
      (node (ref "Q10") (pin "2") (pinfunction "S_2") (pintype "passive"))
      (node (ref "Q11") (pin "2") (pinfunction "S_2") (pintype "passive"))
      (node (ref "Q9") (pin "2") (pinfunction "S_2") (pintype "passive"))
      (node (ref "R152") (pin "1") (pinfunction "1_1") (pintype "passive"))
      (node (ref "R156") (pin "1") (pinfunction "1_1") (pintype "passive"))
      (node (ref "R157") (pin "1") (pinfunction "1_1") (pintype "passive"))
      (node (ref "R161") (pin "1") (pinfunction "1_1") (pintype "passive"))
      (node (ref "R164") (pin "1") (pinfunction "1_1") (pintype "passive"))
      (node (ref "R165") (pin "1") (pinfunction "1_1") (pintype "passive"))
      (node (ref "R170") (pin "1") (pinfunction "1_1") (pintype "passive"))
      (node (ref "U19") (pin "14") (pinfunction "GND_14") (pintype "power_in"))
      (node (ref "U19") (pin "20") (pinfunction "GND_20") (pintype "power_in"))
      (node (ref "U19") (pin "21") (pinfunction "GND_21") (pintype "power_in"))
      (node (ref "U19") (pin "26") (pinfunction "GND_26") (pintype "power_in"))
      (node (ref "U19") (pin "3") (pinfunction "GND_3") (pintype "power_in"))
      (node (ref "U19") (pin "31") (pinfunction "GND_31") (pintype "power_in"))
      (node (ref "U19") (pin "37") (pinfunction "GND_37") (pintype "power_in"))
      (node (ref "U19") (pin "41") (pinfunction "EP_41") (pintype "power_in"))
      (node (ref "U19") (pin "8") (pinfunction "GND_8") (pintype "power_in"))
      (node (ref "U20") (pin "1") (pinfunction "GND_1") (pintype "power_in"))
      (node (ref "U20") (pin "7") (pinfunction "EXP_7") (pintype "power_in"))
      (node (ref "U21") (pin "24") (pinfunction "AVEE_24") (pintype "power_in"))
      (node (ref "U21") (pin "27") (pinfunction "AVEE_27") (pintype "power_in"))
      (node (ref "U21") (pin "37") (pinfunction "AVEE_37") (pintype "power_in"))
      (node (ref "U21") (pin "41") (pinfunction "AVEE_41") (pintype "power_in"))
    )
    (net (code "58") (name "Net-(D37-Pad1)") (class "Default")
      (node (ref "D37") (pin "1") (pinfunction "1_1") (pintype "passive"))
      (node (ref "R151") (pin "1") (pinfunction "1_1") (pintype "passive"))
    )
    (net (code "59") (name "Net-(Q9-G)") (class "Default")
      (node (ref "Q9") (pin "1") (pinfunction "G_1") (pintype "passive"))
      (node (ref "R161") (pin "2") (pinfunction "2_2") (pintype "passive"))
      (node (ref "R162") (pin "1") (pinfunction "1_1") (pintype "passive"))
    )
    (net (code "60") (name "Net-(Q10-D)") (class "Default")
      (node (ref "Q10") (pin "3") (pinfunction "D_3") (pintype "passive"))
      (node (ref "Q11") (pin "1") (pinfunction "G_1") (pintype "passive"))
      (node (ref "R171") (pin "1") (pinfunction "1_1") (pintype "passive"))
    )
    (net (code "61") (name "Net-(U19-I2CEN)") (class "Default")
      (node (ref "R160") (pin "2") (pinfunction "2_2") (pintype "passive"))
      (node (ref "U19") (pin "5") (pinfunction "I2CEN_5") (pintype "input"))
    )
    (net (code "62") (name "Net-(U19-OVS)") (class "Default")
      (node (ref "R163") (pin "2") (pinfunction "2_2") (pintype "passive"))
      (node (ref "U19") (pin "25") (pinfunction "OVS_25") (pintype "input"))
    )
    (net (code "63") (name "Net-(U19-PRE)") (class "Default")
      (node (ref "R156") (pin "2") (pinfunction "2_2") (pintype "passive"))
      (node (ref "U19") (pin "7") (pinfunction "PRE_7") (pintype "input"))
    )
    (net (code "64") (name "Net-(U19-VSADJ)") (class "Default")
      (node (ref "R152") (pin "2") (pinfunction "2_2") (pintype "passive"))
      (node (ref "U19") (pin "30") (pinfunction "VSADJ_30") (pintype "input"))
    )
    (net (code "65") (name "Net-(U19-~{OE})") (class "Default")
      (node (ref "R157") (pin "2") (pinfunction "2_2") (pintype "passive"))
      (node (ref "U19") (pin "6") (pinfunction "~{OE}_6") (pintype "input"))
    )
    (net (code "66") (name "Net-(U21-COMP)") (class "Default")
      (node (ref "C180") (pin "2") (pinfunction "2_2") (pintype "passive"))
      (node (ref "U21") (pin "21") (pinfunction "COMP_21") (pintype "passive"))
    )
    (net (code "67") (name "VCC3V3") (class "Default")
      (node (ref "C167") (pin "1") (pinfunction "1_1") (pintype "passive"))
      (node (ref "C168") (pin "1") (pinfunction "1_1") (pintype "passive"))
      (node (ref "C169") (pin "1") (pinfunction "1_1") (pintype "passive"))
      (node (ref "C170") (pin "1") (pinfunction "1_1") (pintype "passive"))
      (node (ref "C171") (pin "1") (pinfunction "1_1") (pintype "passive"))
      (node (ref "C172") (pin "1") (pinfunction "1_1") (pintype "passive"))
      (node (ref "C173") (pin "1") (pinfunction "1_1") (pintype "passive"))
      (node (ref "C183") (pin "1") (pinfunction "1_1") (pintype "passive"))
      (node (ref "D37") (pin "2") (pinfunction "2_2") (pintype "passive"))
      (node (ref "L13") (pin "1") (pinfunction "1_1") (pintype "passive"))
      (node (ref "R155") (pin "2") (pinfunction "2_2") (pintype "passive"))
      (node (ref "R158") (pin "1") (pinfunction "1_1") (pintype "passive"))
      (node (ref "R159") (pin "1") (pinfunction "1_1") (pintype "passive"))
      (node (ref "R160") (pin "1") (pinfunction "1_1") (pintype "passive"))
      (node (ref "R163") (pin "1") (pinfunction "1_1") (pintype "passive"))
      (node (ref "R168") (pin "2") (pinfunction "2_2") (pintype "passive"))
      (node (ref "R169") (pin "2") (pinfunction "2_2") (pintype "passive"))
      (node (ref "U19") (pin "11") (pinfunction "VCC_11") (pintype "power_in"))
      (node (ref "U19") (pin "17") (pinfunction "VCC_17") (pintype "power_in"))
      (node (ref "U19") (pin "24") (pinfunction "VCC_24") (pintype "power_in"))
      (node (ref "U19") (pin "27") (pinfunction "VCC_27") (pintype "power_in"))
      (node (ref "U19") (pin "34") (pinfunction "VCC_34") (pintype "power_in"))
      (node (ref "U19") (pin "4") (pinfunction "VCC_4") (pintype "power_in"))
      (node (ref "U19") (pin "40") (pinfunction "VCC_40") (pintype "power_in"))
      (node (ref "U21") (pin "33") (pinfunction "VREF_OUT_33") (pintype "passive"))
    )
    (net (code "68") (name "VCC5V") (class "Default")
      (node (ref "C174") (pin "2") (pinfunction "2_2") (pintype "passive"))
      (node (ref "C176") (pin "2") (pinfunction "2_2") (pintype "passive"))
      (node (ref "D50") (pin "2") (pinfunction "2_2") (pintype "passive"))
      (node (ref "U20") (pin "2") (pinfunction "IN_2") (pintype "power_in"))
      (node (ref "U20") (pin "3") (pinfunction "EN_3") (pintype "power_in"))
    )
    (net (code "69") (name "VCC5V0_RX") (class "Default")
      (node (ref "C178") (pin "2") (pinfunction "2_2") (pintype "passive"))
      (node (ref "D49") (pin "2") (pinfunction "2_2") (pintype "passive"))
      (node (ref "D51") (pin "2") (pinfunction "2_2") (pintype "passive"))
      (node (ref "J24") (pin "18") (pinfunction "+5V_Power_18") (pintype "passive"))
      (node (ref "R166") (pin "2") (pinfunction "2_2") (pintype "passive"))
      (node (ref "R167") (pin "2") (pinfunction "2_2") (pintype "passive"))
      (node (ref "R171") (pin "2") (pinfunction "2_2") (pintype "passive"))
      (node (ref "R172") (pin "2") (pinfunction "2_2") (pintype "passive"))
    )
    (net (code "70") (name "unconnected-(J23-Utility_{slash}_HEAC+-Pad14)") (class "Default")
      (node (ref "J23") (pin "14") (pinfunction "Utility_/_HEAC+_14") (pintype "passive"))
    )
    (net (code "71") (name "unconnected-(J24-Utility_{slash}_HEAC+-Pad14)") (class "Default")
      (node (ref "J24") (pin "14") (pinfunction "Utility_/_HEAC+_14") (pintype "passive"))
    )
    (net (code "72") (name "unconnected-(U20-NC-Pad4)") (class "Default")
      (node (ref "U20") (pin "4") (pinfunction "NC_4") (pintype "power_in"))
    )
  )
)
